# first.net
KiCad netlist of a schematic drawn in EAGLE
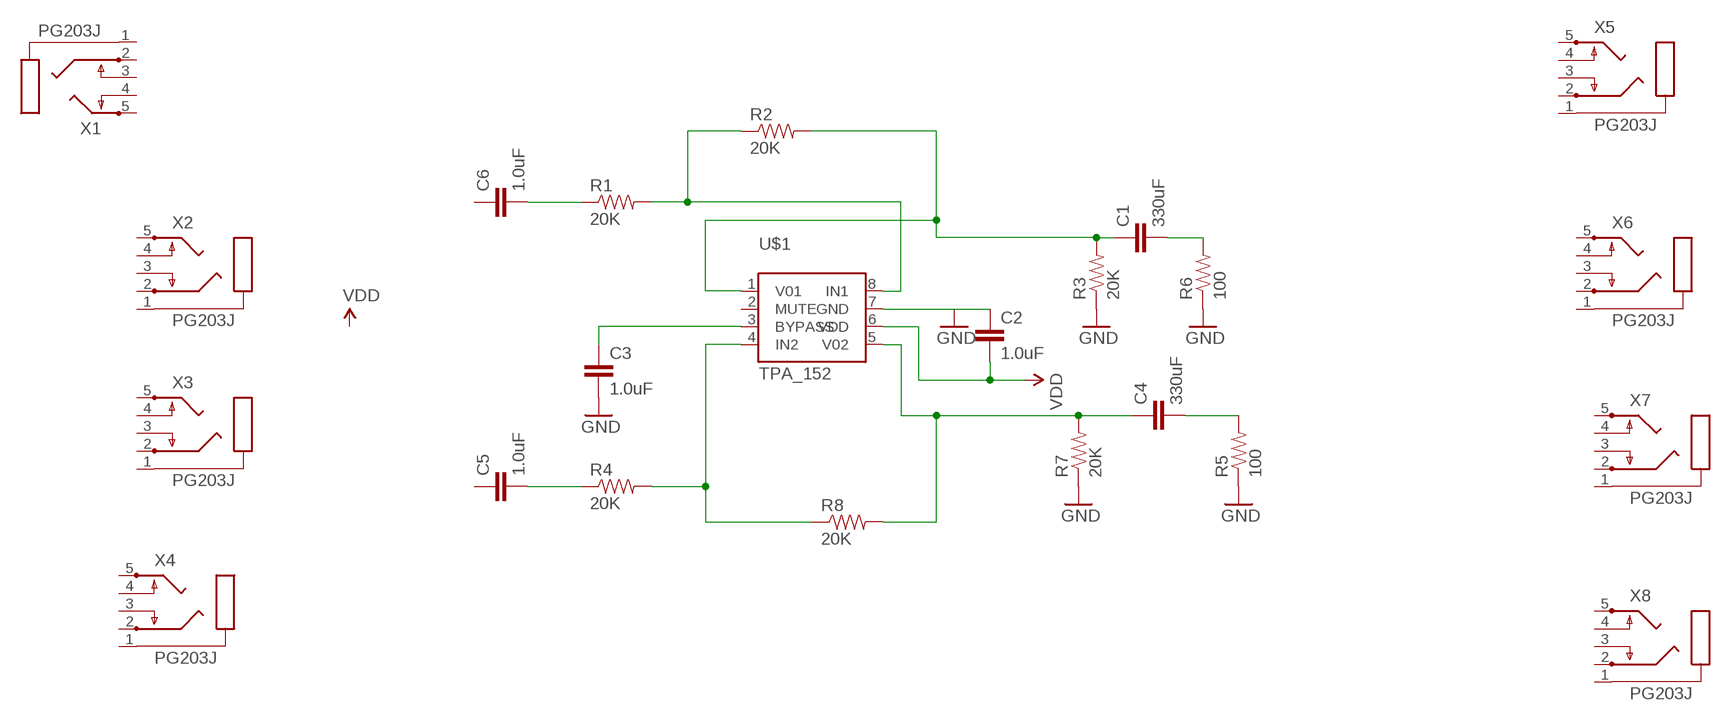
[diagram p0: schematic, sheet 1]

(export (version "E")
  (design (tool "Eeschema 10.0.6"))
  (components
    (comp (ref "C1")
      (value "330uF")
      (footprint "eagle-import:0805")
      (libsource (lib "eagle-import") (part "1.0UF-25V-+80/-20(0805)"))
    )
    (comp (ref "C2")
      (value "1.0uF")
      (footprint "eagle-import:0805")
      (libsource (lib "eagle-import") (part "1.0UF-25V-+80/-20(0805)"))
    )
    (comp (ref "C3")
      (value "1.0uF")
      (footprint "eagle-import:0805")
      (libsource (lib "eagle-import") (part "1.0UF-25V-+80/-20(0805)"))
    )
    (comp (ref "C4")
      (value "330uF")
      (footprint "eagle-import:0805")
      (libsource (lib "eagle-import") (part "1.0UF-25V-+80/-20(0805)"))
    )
    (comp (ref "C5")
      (value "1.0uF")
      (footprint "eagle-import:0805")
      (libsource (lib "eagle-import") (part "1.0UF-25V-+80/-20(0805)"))
    )
    (comp (ref "C6")
      (value "1.0uF")
      (footprint "eagle-import:0805")
      (libsource (lib "eagle-import") (part "1.0UF-25V-+80/-20(0805)"))
    )
    (comp (ref "R1")
      (value "20K")
      (footprint "eagle-import:AXIAL-0.4")
      (libsource (lib "eagle-import") (part "RESISTORPTH-1/4W"))
    )
    (comp (ref "R2")
      (value "20K")
      (footprint "eagle-import:AXIAL-0.4")
      (libsource (lib "eagle-import") (part "RESISTORPTH-1/4W"))
    )
    (comp (ref "R3")
      (value "20K")
      (footprint "eagle-import:AXIAL-0.4")
      (libsource (lib "eagle-import") (part "RESISTORPTH-1/4W"))
    )
    (comp (ref "R4")
      (value "20K")
      (footprint "eagle-import:AXIAL-0.4")
      (libsource (lib "eagle-import") (part "RESISTORPTH-1/4W"))
    )
    (comp (ref "R5")
      (value "100")
      (footprint "eagle-import:AXIAL-0.4")
      (libsource (lib "eagle-import") (part "RESISTORPTH-1/4W"))
    )
    (comp (ref "R6")
      (value "100")
      (footprint "eagle-import:AXIAL-0.4")
      (libsource (lib "eagle-import") (part "RESISTORPTH-1/4W"))
    )
    (comp (ref "R7")
      (value "20K")
      (footprint "eagle-import:AXIAL-0.4")
      (libsource (lib "eagle-import") (part "RESISTORPTH-1/4W"))
    )
    (comp (ref "R8")
      (value "20K")
      (footprint "eagle-import:AXIAL-0.4")
      (libsource (lib "eagle-import") (part "RESISTORPTH-1/4W"))
    )
    (comp (ref "U$1")
      (value "TPA_152")
      (footprint "eagle-import:SOIC8")
      (libsource (lib "eagle-import") (part "TPA_152"))
    )
    (comp (ref "X1")
      (value "PG203J")
      (footprint "eagle-import:PG203J")
      (libsource (lib "eagle-import") (part "PG203J"))
    )
    (comp (ref "X2")
      (value "PG203J")
      (footprint "eagle-import:PG203J")
      (libsource (lib "eagle-import") (part "PG203J"))
    )
    (comp (ref "X3")
      (value "PG203J")
      (footprint "eagle-import:PG203J")
      (libsource (lib "eagle-import") (part "PG203J"))
    )
    (comp (ref "X4")
      (value "PG203J")
      (footprint "eagle-import:PG203J")
      (libsource (lib "eagle-import") (part "PG203J"))
    )
    (comp (ref "X5")
      (value "PG203J")
      (footprint "eagle-import:PG203J")
      (libsource (lib "eagle-import") (part "PG203J"))
    )
    (comp (ref "X6")
      (value "PG203J")
      (footprint "eagle-import:PG203J")
      (libsource (lib "eagle-import") (part "PG203J"))
    )
    (comp (ref "X7")
      (value "PG203J")
      (footprint "eagle-import:PG203J")
      (libsource (lib "eagle-import") (part "PG203J"))
    )
    (comp (ref "X8")
      (value "PG203J")
      (footprint "eagle-import:PG203J")
      (libsource (lib "eagle-import") (part "PG203J"))
    )
  )
  (nets
    (net (code "1") (name "GND") (class "Default")
      (node (ref "C3") (pin "2") (pinfunction "2_2") (pintype "passive"))
      (node (ref "R3") (pin "P$1") (pinfunction "1_P$1") (pintype "passive"))
      (node (ref "R5") (pin "P$1") (pinfunction "1_P$1") (pintype "passive"))
      (node (ref "R6") (pin "P$1") (pinfunction "1_P$1") (pintype "passive"))
      (node (ref "R7") (pin "P$1") (pinfunction "1_P$1") (pintype "passive"))
    )
    (net (code "2") (name "Net-(R1-1)") (class "Default")
      (node (ref "C6") (pin "2") (pinfunction "2_2") (pintype "passive"))
      (node (ref "R1") (pin "P$1") (pinfunction "1_P$1") (pintype "passive"))
    )
    (net (code "3") (name "Net-(R1-2)") (class "Default")
      (node (ref "R1") (pin "P$2") (pinfunction "2_P$2") (pintype "passive"))
      (node (ref "R2") (pin "P$1") (pinfunction "1_P$1") (pintype "passive"))
      (node (ref "U$1") (pin "8") (pinfunction "IN1_8") (pintype "bidirectional"))
    )
    (net (code "4") (name "Net-(R2-2)") (class "Default")
      (node (ref "C1") (pin "1") (pinfunction "1_1") (pintype "passive"))
      (node (ref "R2") (pin "P$2") (pinfunction "2_P$2") (pintype "passive"))
      (node (ref "R3") (pin "P$2") (pinfunction "2_P$2") (pintype "passive"))
      (node (ref "U$1") (pin "1") (pinfunction "V01_1") (pintype "bidirectional"))
    )
    (net (code "5") (name "Net-(R4-1)") (class "Default")
      (node (ref "C5") (pin "2") (pinfunction "2_2") (pintype "passive"))
      (node (ref "R4") (pin "P$1") (pinfunction "1_P$1") (pintype "passive"))
    )
    (net (code "6") (name "Net-(R4-2)") (class "Default")
      (node (ref "R4") (pin "P$2") (pinfunction "2_P$2") (pintype "passive"))
      (node (ref "R8") (pin "P$1") (pinfunction "1_P$1") (pintype "passive"))
      (node (ref "U$1") (pin "4") (pinfunction "IN2_4") (pintype "bidirectional"))
    )
    (net (code "7") (name "Net-(R5-2)") (class "Default")
      (node (ref "C4") (pin "2") (pinfunction "2_2") (pintype "passive"))
      (node (ref "R5") (pin "P$2") (pinfunction "2_P$2") (pintype "passive"))
    )
    (net (code "8") (name "Net-(R6-2)") (class "Default")
      (node (ref "C1") (pin "2") (pinfunction "2_2") (pintype "passive"))
      (node (ref "R6") (pin "P$2") (pinfunction "2_P$2") (pintype "passive"))
    )
    (net (code "9") (name "Net-(R7-2)") (class "Default")
      (node (ref "C4") (pin "1") (pinfunction "1_1") (pintype "passive"))
      (node (ref "R7") (pin "P$2") (pinfunction "2_P$2") (pintype "passive"))
      (node (ref "R8") (pin "P$2") (pinfunction "2_P$2") (pintype "passive"))
      (node (ref "U$1") (pin "5") (pinfunction "V02_5") (pintype "bidirectional"))
    )
    (net (code "10") (name "Net-(U$1-BYPASS)") (class "Default")
      (node (ref "C3") (pin "1") (pinfunction "1_1") (pintype "passive"))
      (node (ref "U$1") (pin "3") (pinfunction "BYPASS_3") (pintype "bidirectional"))
    )
    (net (code "11") (name "Net-(U$1-GND)") (class "Default")
      (node (ref "C2") (pin "1") (pinfunction "1_1") (pintype "passive"))
      (node (ref "U$1") (pin "7") (pinfunction "GND_7") (pintype "bidirectional"))
    )
    (net (code "12") (name "VDD") (class "Default")
      (node (ref "C2") (pin "2") (pinfunction "2_2") (pintype "passive"))
      (node (ref "U$1") (pin "6") (pinfunction "VDD_6") (pintype "bidirectional"))
    )
    (net (code "13") (name "unconnected-(C5-Pad1)") (class "Default")
      (node (ref "C5") (pin "1") (pinfunction "1_1") (pintype "passive"))
    )
    (net (code "14") (name "unconnected-(C6-Pad1)") (class "Default")
      (node (ref "C6") (pin "1") (pinfunction "1_1") (pintype "passive"))
    )
    (net (code "15") (name "unconnected-(U$1-MUTE-Pad2)") (class "Default")
      (node (ref "U$1") (pin "2") (pinfunction "MUTE_2") (pintype "bidirectional"))
    )
    (net (code "16") (name "unconnected-(X1-Pad1)") (class "Default")
      (node (ref "X1") (pin "1") (pinfunction "1_1") (pintype "passive"))
    )
    (net (code "17") (name "unconnected-(X1-Pad2)") (class "Default")
      (node (ref "X1") (pin "2") (pinfunction "2_2") (pintype "passive"))
    )
    (net (code "18") (name "unconnected-(X1-Pad3)") (class "Default")
      (node (ref "X1") (pin "3") (pinfunction "3_3") (pintype "passive"))
    )
    (net (code "19") (name "unconnected-(X1-Pad4)") (class "Default")
      (node (ref "X1") (pin "4") (pinfunction "4_4") (pintype "passive"))
    )
    (net (code "20") (name "unconnected-(X1-Pad5)") (class "Default")
      (node (ref "X1") (pin "5") (pinfunction "5_5") (pintype "passive"))
    )
    (net (code "21") (name "unconnected-(X2-Pad1)") (class "Default")
      (node (ref "X2") (pin "1") (pinfunction "1_1") (pintype "passive"))
    )
    (net (code "22") (name "unconnected-(X2-Pad2)") (class "Default")
      (node (ref "X2") (pin "2") (pinfunction "2_2") (pintype "passive"))
    )
    (net (code "23") (name "unconnected-(X2-Pad3)") (class "Default")
      (node (ref "X2") (pin "3") (pinfunction "3_3") (pintype "passive"))
    )
    (net (code "24") (name "unconnected-(X2-Pad4)") (class "Default")
      (node (ref "X2") (pin "4") (pinfunction "4_4") (pintype "passive"))
    )
    (net (code "25") (name "unconnected-(X2-Pad5)") (class "Default")
      (node (ref "X2") (pin "5") (pinfunction "5_5") (pintype "passive"))
    )
    (net (code "26") (name "unconnected-(X3-Pad1)") (class "Default")
      (node (ref "X3") (pin "1") (pinfunction "1_1") (pintype "passive"))
    )
    (net (code "27") (name "unconnected-(X3-Pad2)") (class "Default")
      (node (ref "X3") (pin "2") (pinfunction "2_2") (pintype "passive"))
    )
    (net (code "28") (name "unconnected-(X3-Pad3)") (class "Default")
      (node (ref "X3") (pin "3") (pinfunction "3_3") (pintype "passive"))
    )
    (net (code "29") (name "unconnected-(X3-Pad4)") (class "Default")
      (node (ref "X3") (pin "4") (pinfunction "4_4") (pintype "passive"))
    )
    (net (code "30") (name "unconnected-(X3-Pad5)") (class "Default")
      (node (ref "X3") (pin "5") (pinfunction "5_5") (pintype "passive"))
    )
    (net (code "31") (name "unconnected-(X4-Pad1)") (class "Default")
      (node (ref "X4") (pin "1") (pinfunction "1_1") (pintype "passive"))
    )
    (net (code "32") (name "unconnected-(X4-Pad2)") (class "Default")
      (node (ref "X4") (pin "2") (pinfunction "2_2") (pintype "passive"))
    )
    (net (code "33") (name "unconnected-(X4-Pad3)") (class "Default")
      (node (ref "X4") (pin "3") (pinfunction "3_3") (pintype "passive"))
    )
    (net (code "34") (name "unconnected-(X4-Pad4)") (class "Default")
      (node (ref "X4") (pin "4") (pinfunction "4_4") (pintype "passive"))
    )
    (net (code "35") (name "unconnected-(X4-Pad5)") (class "Default")
      (node (ref "X4") (pin "5") (pinfunction "5_5") (pintype "passive"))
    )
    (net (code "36") (name "unconnected-(X5-Pad1)") (class "Default")
      (node (ref "X5") (pin "1") (pinfunction "1_1") (pintype "passive"))
    )
    (net (code "37") (name "unconnected-(X5-Pad2)") (class "Default")
      (node (ref "X5") (pin "2") (pinfunction "2_2") (pintype "passive"))
    )
    (net (code "38") (name "unconnected-(X5-Pad3)") (class "Default")
      (node (ref "X5") (pin "3") (pinfunction "3_3") (pintype "passive"))
    )
    (net (code "39") (name "unconnected-(X5-Pad4)") (class "Default")
      (node (ref "X5") (pin "4") (pinfunction "4_4") (pintype "passive"))
    )
    (net (code "40") (name "unconnected-(X5-Pad5)") (class "Default")
      (node (ref "X5") (pin "5") (pinfunction "5_5") (pintype "passive"))
    )
    (net (code "41") (name "unconnected-(X6-Pad1)") (class "Default")
      (node (ref "X6") (pin "1") (pinfunction "1_1") (pintype "passive"))
    )
    (net (code "42") (name "unconnected-(X6-Pad2)") (class "Default")
      (node (ref "X6") (pin "2") (pinfunction "2_2") (pintype "passive"))
    )
    (net (code "43") (name "unconnected-(X6-Pad3)") (class "Default")
      (node (ref "X6") (pin "3") (pinfunction "3_3") (pintype "passive"))
    )
    (net (code "44") (name "unconnected-(X6-Pad4)") (class "Default")
      (node (ref "X6") (pin "4") (pinfunction "4_4") (pintype "passive"))
    )
    (net (code "45") (name "unconnected-(X6-Pad5)") (class "Default")
      (node (ref "X6") (pin "5") (pinfunction "5_5") (pintype "passive"))
    )
    (net (code "46") (name "unconnected-(X7-Pad1)") (class "Default")
      (node (ref "X7") (pin "1") (pinfunction "1_1") (pintype "passive"))
    )
    (net (code "47") (name "unconnected-(X7-Pad2)") (class "Default")
      (node (ref "X7") (pin "2") (pinfunction "2_2") (pintype "passive"))
    )
    (net (code "48") (name "unconnected-(X7-Pad3)") (class "Default")
      (node (ref "X7") (pin "3") (pinfunction "3_3") (pintype "passive"))
    )
    (net (code "49") (name "unconnected-(X7-Pad4)") (class "Default")
      (node (ref "X7") (pin "4") (pinfunction "4_4") (pintype "passive"))
    )
    (net (code "50") (name "unconnected-(X7-Pad5)") (class "Default")
      (node (ref "X7") (pin "5") (pinfunction "5_5") (pintype "passive"))
    )
    (net (code "51") (name "unconnected-(X8-Pad1)") (class "Default")
      (node (ref "X8") (pin "1") (pinfunction "1_1") (pintype "passive"))
    )
    (net (code "52") (name "unconnected-(X8-Pad2)") (class "Default")
      (node (ref "X8") (pin "2") (pinfunction "2_2") (pintype "passive"))
    )
    (net (code "53") (name "unconnected-(X8-Pad3)") (class "Default")
      (node (ref "X8") (pin "3") (pinfunction "3_3") (pintype "passive"))
    )
    (net (code "54") (name "unconnected-(X8-Pad4)") (class "Default")
      (node (ref "X8") (pin "4") (pinfunction "4_4") (pintype "passive"))
    )
    (net (code "55") (name "unconnected-(X8-Pad5)") (class "Default")
      (node (ref "X8") (pin "5") (pinfunction "5_5") (pintype "passive"))
    )
  )
)
